# MAX3488AEGSA.net
KiCad netlist of a schematic drawn in Altium Designer
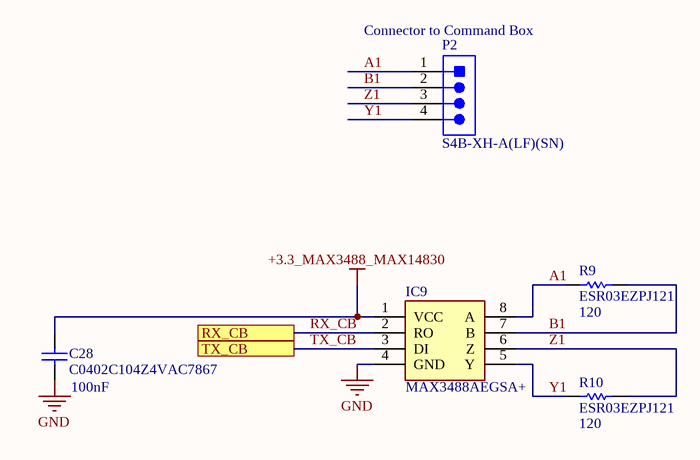
[diagram p0: MAX3488AEGSA+.SchDoc]

(export (version "E")
  (design (tool "Eeschema 10.0.6"))
  (components
    (comp (ref "C28")
      (value "C0402C104Z4VAC7867")
      (footprint "CAPC1005X60X30LL05T10")
      (fields (field (name "MANUFACTURER") "Kemet") (field (name "SPEC") "100nF"))
      (libsource (lib "Altium Content Vault") (part "CAP"))
    )
    (comp (ref "IC9")
      (value "MAX3488AEGSA+")
      (footprint "PcbLib1:SOIC127P600X175-8N")
      (description "Integrated Circuit")
      (fields (field (name "MOUSER PART NUMBER") "700-MAX3488AEGSA+"))
      (libsource (lib "*") (part "MAX3488AEGSA+"))
    )
    (comp (ref "P2")
      (value "S4B-XH-A(LF)(SN)")
      (footprint "JST-S4B-XH-A(LF)(SN)_V")
      (libsource (lib "Altium Content Vault") (part "CN-1P-M-R4"))
    )
    (comp (ref "R9")
      (value "ESR03EZPJ121")
      (footprint "1608[0603]")
      (description "Resistor")
      (fields (field (name "ALTIUM_VALUE") "120") (field (name "PUBLISHER") "Altium Limited"))
      (libsource (lib "Miscellaneous Devices") (part "Res1"))
    )
    (comp (ref "R10")
      (value "ESR03EZPJ121")
      (footprint "1608[0603]")
      (description "Resistor")
      (fields (field (name "ALTIUM_VALUE") "120") (field (name "PUBLISHER") "Altium Limited"))
      (libsource (lib "Miscellaneous Devices") (part "Res1"))
    )
  )
  (nets
    (net (code "1") (name "+3.3_MAX3488_MAX14830") (class "Default")
      (node (ref "C28") (pin "2") (pinfunction "2_2") (pintype "passive"))
      (node (ref "IC9") (pin "1") (pinfunction "VCC_1") (pintype "passive"))
    )
    (net (code "2") (name "/A1") (class "Default")
      (node (ref "IC9") (pin "8") (pinfunction "A_8") (pintype "passive"))
      (node (ref "P2") (pin "1") (pinfunction "1_1") (pintype "passive"))
      (node (ref "R9") (pin "1") (pinfunction "1_1") (pintype "passive"))
    )
    (net (code "3") (name "/B1") (class "Default")
      (node (ref "IC9") (pin "7") (pinfunction "B_7") (pintype "passive"))
      (node (ref "P2") (pin "2") (pinfunction "2_2") (pintype "passive"))
      (node (ref "R9") (pin "2") (pinfunction "2_2") (pintype "passive"))
    )
    (net (code "4") (name "/RX_CB") (class "Default")
      (node (ref "IC9") (pin "2") (pinfunction "RO_2") (pintype "passive"))
    )
    (net (code "5") (name "/TX_CB") (class "Default")
      (node (ref "IC9") (pin "3") (pinfunction "DI_3") (pintype "passive"))
    )
    (net (code "6") (name "/Y1") (class "Default")
      (node (ref "IC9") (pin "5") (pinfunction "Y_5") (pintype "passive"))
      (node (ref "P2") (pin "4") (pinfunction "4_4") (pintype "passive"))
      (node (ref "R10") (pin "1") (pinfunction "1_1") (pintype "passive"))
    )
    (net (code "7") (name "/Z1") (class "Default")
      (node (ref "IC9") (pin "6") (pinfunction "Z_6") (pintype "passive"))
      (node (ref "P2") (pin "3") (pinfunction "3_3") (pintype "passive"))
      (node (ref "R10") (pin "2") (pinfunction "2_2") (pintype "passive"))
    )
    (net (code "8") (name "GND") (class "Default")
      (node (ref "C28") (pin "1") (pinfunction "1_1") (pintype "passive"))
      (node (ref "IC9") (pin "4") (pinfunction "GND_4") (pintype "passive"))
    )
  )
)
